# CT310_V1_0.net
KiCad netlist of a schematic drawn in Altium Designer
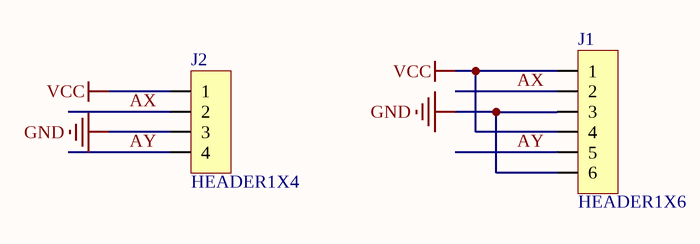
[diagram p0: CT310高端控制盒右摇杆电路V1.0.SchDoc]

(export (version "E")
  (design (tool "Eeschema 10.0.6"))
  (components
    (comp (ref "J1")
      (value "HEADER1X6")
      (footprint "H20JH")
      (libsource (lib "Connector Class") (part "HEADER1X6"))
    )
    (comp (ref "J2")
      (value "HEADER1X4")
      (footprint "ZH1X4WT-1.5")
      (libsource (lib "Connector Class") (part "HEADER1X4"))
    )
  )
  (nets
    (net (code "1") (name "/AX") (class "Default")
      (node (ref "J1") (pin "2") (pinfunction "2_2") (pintype "passive"))
      (node (ref "J2") (pin "2") (pinfunction "2_2") (pintype "passive"))
    )
    (net (code "2") (name "/AY") (class "Default")
      (node (ref "J1") (pin "5") (pinfunction "5_5") (pintype "passive"))
      (node (ref "J2") (pin "4") (pinfunction "4_4") (pintype "passive"))
    )
    (net (code "3") (name "GND") (class "Default")
      (node (ref "J1") (pin "3") (pinfunction "3_3") (pintype "passive"))
      (node (ref "J1") (pin "6") (pinfunction "6_6") (pintype "passive"))
      (node (ref "J2") (pin "3") (pinfunction "3_3") (pintype "passive"))
    )
    (net (code "4") (name "VCC") (class "Default")
      (node (ref "J1") (pin "1") (pinfunction "1_1") (pintype "passive"))
      (node (ref "J1") (pin "4") (pinfunction "4_4") (pintype "passive"))
      (node (ref "J2") (pin "1") (pinfunction "1_1") (pintype "passive"))
    )
  )
)
